# gate.net
KiCad netlist of a schematic drawn in EAGLE
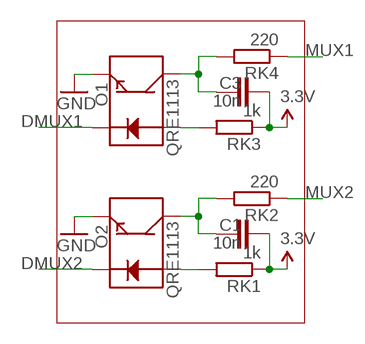
[diagram p0: schematic, sheet 1]

(export (version "E")
  (design (tool "Eeschema 10.0.6"))
  (components
    (comp (ref "C1")
      (value "10n")
      (footprint "eagle-import:C0805")
      (libsource (lib "eagle-import") (part "C-EUC0805"))
    )
    (comp (ref "C3")
      (value "10n")
      (footprint "eagle-import:C0805")
      (libsource (lib "eagle-import") (part "C-EUC0805"))
    )
    (comp (ref "O1")
      (value "QRE1113")
      (footprint "eagle-import:QRE1113")
      (libsource (lib "eagle-import") (part "QRE1113"))
    )
    (comp (ref "O2")
      (value "QRE1113")
      (footprint "eagle-import:QRE1113")
      (libsource (lib "eagle-import") (part "QRE1113"))
    )
    (comp (ref "RK1")
      (value "1k")
      (footprint "eagle-import:M0805")
      (libsource (lib "eagle-import") (part "R-EU_M0805"))
    )
    (comp (ref "RK2")
      (value "220")
      (footprint "eagle-import:M0805")
      (libsource (lib "eagle-import") (part "R-EU_M0805"))
    )
    (comp (ref "RK3")
      (value "1k")
      (footprint "eagle-import:M0805")
      (libsource (lib "eagle-import") (part "R-EU_M0805"))
    )
    (comp (ref "RK4")
      (value "220")
      (footprint "eagle-import:M0805")
      (libsource (lib "eagle-import") (part "R-EU_M0805"))
    )
  )
  (nets
    (net (code "1") (name "/DMUX1") (class "Default")
      (node (ref "O1") (pin "2") (pinfunction "K_2") (pintype "bidirectional"))
    )
    (net (code "2") (name "/DMUX2") (class "Default")
      (node (ref "O2") (pin "2") (pinfunction "K_2") (pintype "bidirectional"))
    )
    (net (code "3") (name "/MUX1") (class "Default")
      (node (ref "RK4") (pin "1") (pinfunction "1_1") (pintype "passive"))
    )
    (net (code "4") (name "/MUX2") (class "Default")
      (node (ref "RK2") (pin "1") (pinfunction "1_1") (pintype "passive"))
    )
    (net (code "5") (name "3.3V") (class "Default")
      (node (ref "C1") (pin "2") (pinfunction "2_2") (pintype "passive"))
      (node (ref "C3") (pin "2") (pinfunction "2_2") (pintype "passive"))
      (node (ref "RK1") (pin "1") (pinfunction "1_1") (pintype "passive"))
      (node (ref "RK3") (pin "1") (pinfunction "1_1") (pintype "passive"))
    )
    (net (code "6") (name "GND") (class "Default")
      (node (ref "O1") (pin "4") (pinfunction "E_4") (pintype "bidirectional"))
      (node (ref "O2") (pin "4") (pinfunction "E_4") (pintype "bidirectional"))
    )
    (net (code "7") (name "Net-(O1-A)") (class "Default")
      (node (ref "O1") (pin "1") (pinfunction "A_1") (pintype "bidirectional"))
      (node (ref "RK3") (pin "2") (pinfunction "2_2") (pintype "passive"))
    )
    (net (code "8") (name "Net-(O1-C)") (class "Default")
      (node (ref "C3") (pin "1") (pinfunction "1_1") (pintype "passive"))
      (node (ref "O1") (pin "3") (pinfunction "C_3") (pintype "bidirectional"))
      (node (ref "RK4") (pin "2") (pinfunction "2_2") (pintype "passive"))
    )
    (net (code "9") (name "Net-(O2-A)") (class "Default")
      (node (ref "O2") (pin "1") (pinfunction "A_1") (pintype "bidirectional"))
      (node (ref "RK1") (pin "2") (pinfunction "2_2") (pintype "passive"))
    )
    (net (code "10") (name "Net-(O2-C)") (class "Default")
      (node (ref "C1") (pin "1") (pinfunction "1_1") (pintype "passive"))
      (node (ref "O2") (pin "3") (pinfunction "C_3") (pintype "bidirectional"))
      (node (ref "RK2") (pin "2") (pinfunction "2_2") (pintype "passive"))
    )
  )
)
